# untitled.net
KiCad netlist of a schematic drawn in EAGLE
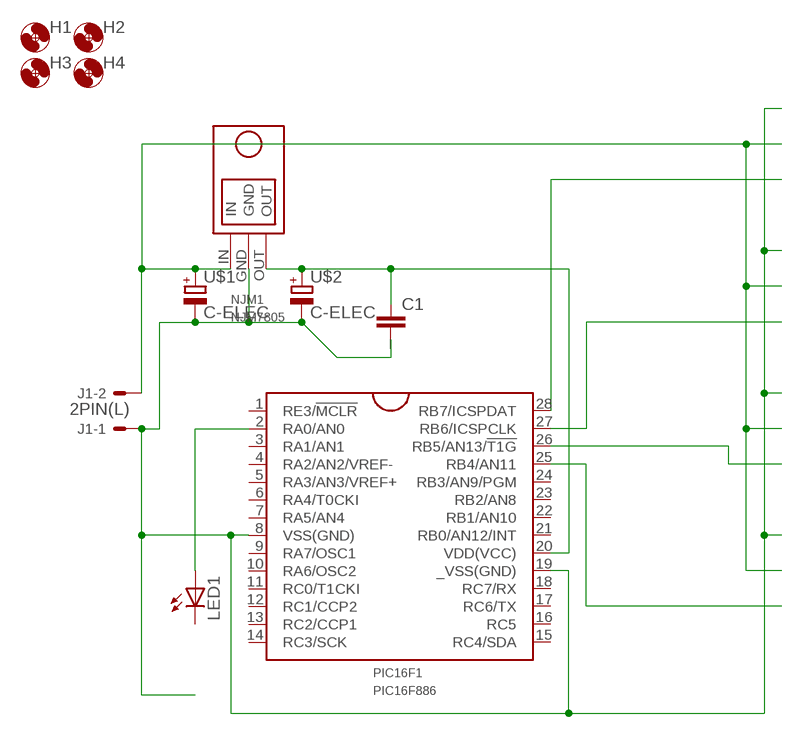
[diagram p0: schematic, sheet 1]

(export (version "E")
  (design (tool "Eeschema 10.0.6"))
  (components
    (comp (ref "C1")
      (value "C-")
      (footprint "eagle-import:C-2.54")
      (libsource (lib "eagle-import") (part "C-"))
    )
    (comp (ref "H1")
      (value "HOLE3.3M3BOLT")
      (footprint "eagle-import:HOLE3.3")
      (libsource (lib "eagle-import") (part "HOLE3.3M3BOLT"))
    )
    (comp (ref "H2")
      (value "HOLE3.3M3BOLT")
      (footprint "eagle-import:HOLE3.3")
      (libsource (lib "eagle-import") (part "HOLE3.3M3BOLT"))
    )
    (comp (ref "H3")
      (value "HOLE3.3M3BOLT")
      (footprint "eagle-import:HOLE3.3")
      (libsource (lib "eagle-import") (part "HOLE3.3M3BOLT"))
    )
    (comp (ref "H4")
      (value "HOLE3.3M3BOLT")
      (footprint "eagle-import:HOLE3.3")
      (libsource (lib "eagle-import") (part "HOLE3.3M3BOLT"))
    )
    (comp (ref "J1")
      (value "2PIN(L)")
      (footprint "eagle-import:2PL")
      (libsource (lib "eagle-import") (part "2PIN(L)"))
    )
    (comp (ref "LED1")
      (value "LED")
      (footprint "eagle-import:LED5MM")
      (libsource (lib "eagle-import") (part "LED"))
    )
    (comp (ref "NJM1")
      (value "NJM7805")
      (footprint "eagle-import:NJM7805")
      (libsource (lib "eagle-import") (part "NJM7805"))
    )
    (comp (ref "PIC16F1")
      (value "PIC16F886")
      (footprint "eagle-import:DIL28-3")
      (libsource (lib "eagle-import") (part "PIC16F886"))
    )
    (comp (ref "U$1")
      (value "C-ELEC")
      (footprint "eagle-import:C-6MM")
      (libsource (lib "eagle-import") (part "C-ELEC"))
    )
    (comp (ref "U$2")
      (value "C-ELEC")
      (footprint "eagle-import:C-6MM")
      (libsource (lib "eagle-import") (part "C-ELEC"))
    )
  )
  (nets
    (net (code "1") (name "Net-(J1A-S)") (class "Default")
      (node (ref "J1") (pin "1") (pinfunction "S_1") (pintype "passive"))
      (node (ref "NJM1") (pin "GND") (pinfunction "GND_GND") (pintype "bidirectional"))
      (node (ref "PIC16F1") (pin "19") (pinfunction "_VSS(GND)_19") (pintype "power_in"))
      (node (ref "PIC16F1") (pin "8") (pinfunction "VSS(GND)_8") (pintype "power_in"))
      (node (ref "U$1") (pin "-") (pinfunction "-_-") (pintype "passive"))
      (node (ref "U$2") (pin "-") (pinfunction "-_-") (pintype "passive"))
    )
    (net (code "2") (name "Net-(J1B-S)") (class "Default")
      (node (ref "J1") (pin "2") (pinfunction "S_2") (pintype "passive"))
      (node (ref "NJM1") (pin "IN") (pinfunction "IN_IN") (pintype "bidirectional"))
      (node (ref "U$1") (pin "+") (pinfunction "+_+") (pintype "passive"))
    )
    (net (code "3") (name "Net-(PIC16F1-RA0{slash}AN0)") (class "Default")
      (node (ref "LED1") (pin "A") (pinfunction "A_A") (pintype "passive"))
      (node (ref "PIC16F1") (pin "2") (pinfunction "RA0/AN0_2") (pintype "bidirectional"))
    )
    (net (code "4") (name "Net-(PIC16F1-VDD(VCC))") (class "Default")
      (node (ref "NJM1") (pin "OUT") (pinfunction "OUT_OUT") (pintype "bidirectional"))
      (node (ref "PIC16F1") (pin "20") (pinfunction "VDD(VCC)_20") (pintype "power_in"))
      (node (ref "U$2") (pin "+") (pinfunction "+_+") (pintype "passive"))
    )
    (net (code "5") (name "unconnected-(C1-1-PadP$1)") (class "Default")
      (node (ref "C1") (pin "P$1") (pinfunction "1_P$1") (pintype "passive"))
    )
    (net (code "6") (name "unconnected-(C1-2-PadP$2)") (class "Default")
      (node (ref "C1") (pin "P$2") (pinfunction "2_P$2") (pintype "passive"))
    )
    (net (code "7") (name "unconnected-(LED1-C-PadK)") (class "Default")
      (node (ref "LED1") (pin "K") (pinfunction "C_K") (pintype "passive"))
    )
    (net (code "8") (name "unconnected-(PIC16F1-RA1{slash}AN1-Pad3)") (class "Default")
      (node (ref "PIC16F1") (pin "3") (pinfunction "RA1/AN1_3") (pintype "bidirectional"))
    )
    (net (code "9") (name "unconnected-(PIC16F1-RA2{slash}AN2{slash}VREF--Pad4)") (class "Default")
      (node (ref "PIC16F1") (pin "4") (pinfunction "RA2/AN2/VREF-_4") (pintype "bidirectional"))
    )
    (net (code "10") (name "unconnected-(PIC16F1-RA3{slash}AN3{slash}VREF+-Pad5)") (class "Default")
      (node (ref "PIC16F1") (pin "5") (pinfunction "RA3/AN3/VREF+_5") (pintype "bidirectional"))
    )
    (net (code "11") (name "unconnected-(PIC16F1-RA4{slash}T0CKI-Pad6)") (class "Default")
      (node (ref "PIC16F1") (pin "6") (pinfunction "RA4/T0CKI_6") (pintype "bidirectional"))
    )
    (net (code "12") (name "unconnected-(PIC16F1-RA5{slash}AN4-Pad7)") (class "Default")
      (node (ref "PIC16F1") (pin "7") (pinfunction "RA5/AN4_7") (pintype "bidirectional"))
    )
    (net (code "13") (name "unconnected-(PIC16F1-RA6{slash}OSC2-Pad10)") (class "Default")
      (node (ref "PIC16F1") (pin "10") (pinfunction "RA6/OSC2_10") (pintype "bidirectional"))
    )
    (net (code "14") (name "unconnected-(PIC16F1-RA7{slash}OSC1-Pad9)") (class "Default")
      (node (ref "PIC16F1") (pin "9") (pinfunction "RA7/OSC1_9") (pintype "bidirectional"))
    )
    (net (code "15") (name "unconnected-(PIC16F1-RB0{slash}AN12{slash}INT-Pad21)") (class "Default")
      (node (ref "PIC16F1") (pin "21") (pinfunction "RB0/AN12/INT_21") (pintype "bidirectional"))
    )
    (net (code "16") (name "unconnected-(PIC16F1-RB1{slash}AN10-Pad22)") (class "Default")
      (node (ref "PIC16F1") (pin "22") (pinfunction "RB1/AN10_22") (pintype "bidirectional"))
    )
    (net (code "17") (name "unconnected-(PIC16F1-RB2{slash}AN8-Pad23)") (class "Default")
      (node (ref "PIC16F1") (pin "23") (pinfunction "RB2/AN8_23") (pintype "bidirectional"))
    )
    (net (code "18") (name "unconnected-(PIC16F1-RB3{slash}AN9{slash}PGM-Pad24)") (class "Default")
      (node (ref "PIC16F1") (pin "24") (pinfunction "RB3/AN9/PGM_24") (pintype "bidirectional"))
    )
    (net (code "19") (name "unconnected-(PIC16F1-RB4{slash}AN11-Pad25)") (class "Default")
      (node (ref "PIC16F1") (pin "25") (pinfunction "RB4/AN11_25") (pintype "bidirectional"))
    )
    (net (code "20") (name "unconnected-(PIC16F1-RB5{slash}AN13{slash}~{T1G}-Pad26)") (class "Default")
      (node (ref "PIC16F1") (pin "26") (pinfunction "RB5/AN13/~{T1G}_26") (pintype "bidirectional"))
    )
    (net (code "21") (name "unconnected-(PIC16F1-RB6{slash}ICSPCLK-Pad27)") (class "Default")
      (node (ref "PIC16F1") (pin "27") (pinfunction "RB6/ICSPCLK_27") (pintype "bidirectional"))
    )
    (net (code "22") (name "unconnected-(PIC16F1-RB7{slash}ICSPDAT-Pad28)") (class "Default")
      (node (ref "PIC16F1") (pin "28") (pinfunction "RB7/ICSPDAT_28") (pintype "bidirectional"))
    )
    (net (code "23") (name "unconnected-(PIC16F1-RC0{slash}T1CKI-Pad11)") (class "Default")
      (node (ref "PIC16F1") (pin "11") (pinfunction "RC0/T1CKI_11") (pintype "bidirectional"))
    )
    (net (code "24") (name "unconnected-(PIC16F1-RC1{slash}CCP2-Pad12)") (class "Default")
      (node (ref "PIC16F1") (pin "12") (pinfunction "RC1/CCP2_12") (pintype "bidirectional"))
    )
    (net (code "25") (name "unconnected-(PIC16F1-RC2{slash}CCP1-Pad13)") (class "Default")
      (node (ref "PIC16F1") (pin "13") (pinfunction "RC2/CCP1_13") (pintype "bidirectional"))
    )
    (net (code "26") (name "unconnected-(PIC16F1-RC3{slash}SCK-Pad14)") (class "Default")
      (node (ref "PIC16F1") (pin "14") (pinfunction "RC3/SCK_14") (pintype "bidirectional"))
    )
    (net (code "27") (name "unconnected-(PIC16F1-RC4{slash}SDA-Pad15)") (class "Default")
      (node (ref "PIC16F1") (pin "15") (pinfunction "RC4/SDA_15") (pintype "bidirectional"))
    )
    (net (code "28") (name "unconnected-(PIC16F1-RC5-Pad16)") (class "Default")
      (node (ref "PIC16F1") (pin "16") (pinfunction "RC5_16") (pintype "bidirectional"))
    )
    (net (code "29") (name "unconnected-(PIC16F1-RC6{slash}TX-Pad17)") (class "Default")
      (node (ref "PIC16F1") (pin "17") (pinfunction "RC6/TX_17") (pintype "bidirectional"))
    )
    (net (code "30") (name "unconnected-(PIC16F1-RC7{slash}RX-Pad18)") (class "Default")
      (node (ref "PIC16F1") (pin "18") (pinfunction "RC7/RX_18") (pintype "bidirectional"))
    )
    (net (code "31") (name "unconnected-(PIC16F1-RE3{slash}~{MCLR}-Pad1)") (class "Default")
      (node (ref "PIC16F1") (pin "1") (pinfunction "RE3/~{MCLR}_1") (pintype "bidirectional"))
    )
  )
)
